# adapter_1x1.net
KiCad netlist of a schematic drawn in EAGLE
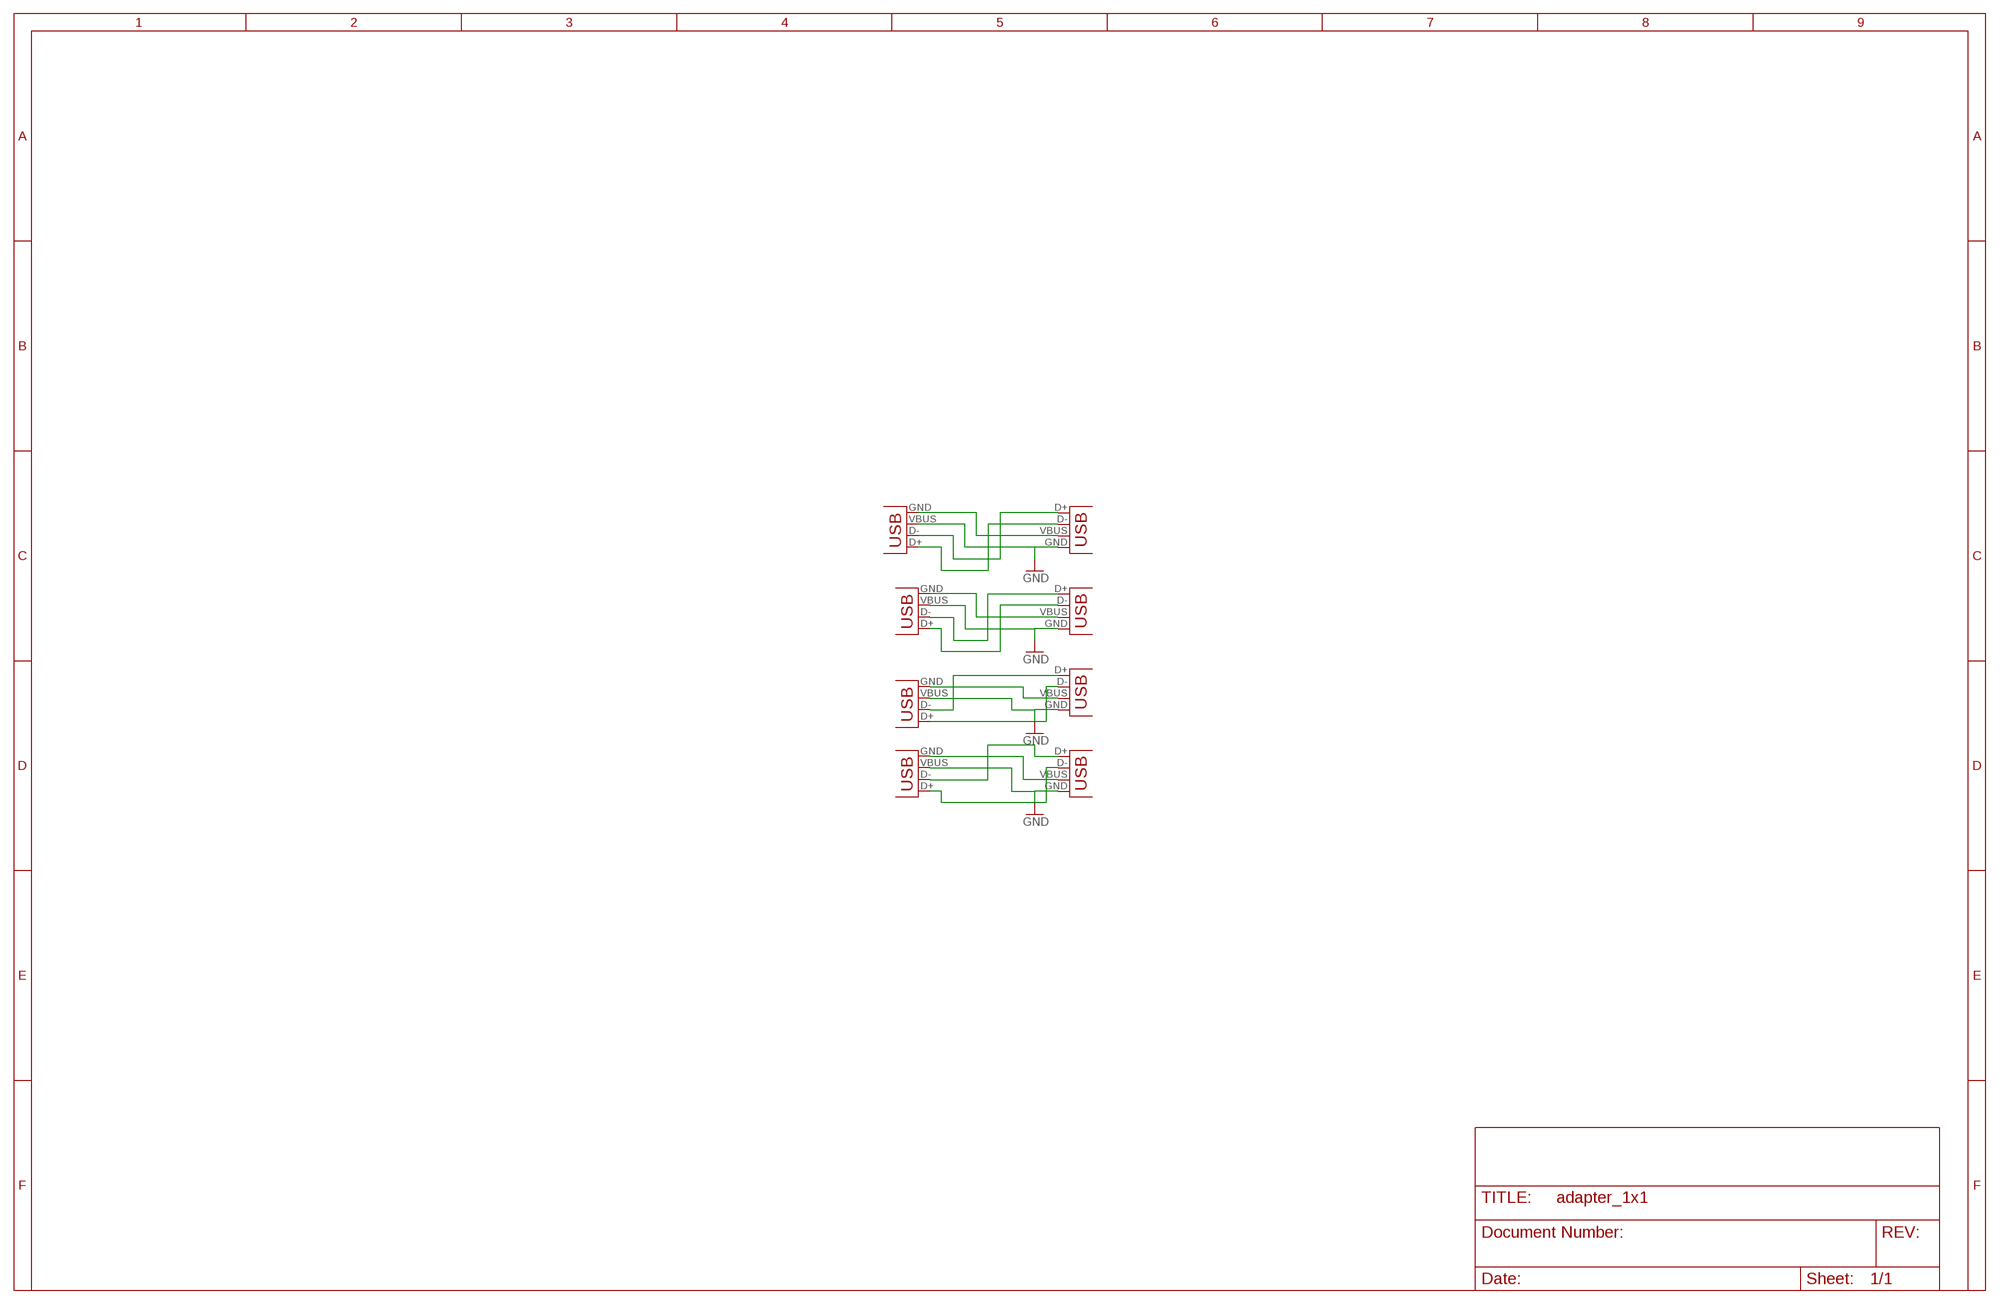
[diagram p0: schematic, sheet 1]

(export (version "E")
  (design (tool "Eeschema 10.0.6"))
  (components
    (comp (ref "X1")
      (value "USB-A-HU")
      (footprint "eagle-import:USB-A-HU")
      (libsource (lib "eagle-import") (part "USB-A-HU"))
    )
    (comp (ref "X2")
      (value "USB-A-HU")
      (footprint "eagle-import:USB-A-HU")
      (libsource (lib "eagle-import") (part "USB-A-HU"))
    )
    (comp (ref "X3")
      (value "USB-A-HU")
      (footprint "eagle-import:USB-A-HU")
      (libsource (lib "eagle-import") (part "USB-A-HU"))
    )
    (comp (ref "X4")
      (value "USB-A-HU")
      (footprint "eagle-import:USB-A-HU")
      (libsource (lib "eagle-import") (part "USB-A-HU"))
    )
    (comp (ref "X5")
      (value "USB-A-HU")
      (footprint "eagle-import:USB-A-HU")
      (libsource (lib "eagle-import") (part "USB-A-HU"))
    )
    (comp (ref "X6")
      (value "USB-A-HU")
      (footprint "eagle-import:USB-A-HU")
      (libsource (lib "eagle-import") (part "USB-A-HU"))
    )
    (comp (ref "X7")
      (value "USB-A-HU")
      (footprint "eagle-import:USB-A-HU")
      (libsource (lib "eagle-import") (part "USB-A-HU"))
    )
    (comp (ref "X8")
      (value "USB-A-HU")
      (footprint "eagle-import:USB-A-HU")
      (libsource (lib "eagle-import") (part "USB-A-HU"))
    )
  )
  (nets
    (net (code "1") (name "GND") (class "Default")
      (node (ref "X1") (pin "GND") (pinfunction "GND_GND") (pintype "bidirectional"))
      (node (ref "X2") (pin "GND") (pinfunction "GND_GND") (pintype "bidirectional"))
      (node (ref "X3") (pin "GND") (pinfunction "GND_GND") (pintype "bidirectional"))
      (node (ref "X4") (pin "GND") (pinfunction "GND_GND") (pintype "bidirectional"))
      (node (ref "X5") (pin "VBUS") (pinfunction "VBUS_VBUS") (pintype "bidirectional"))
      (node (ref "X6") (pin "VBUS") (pinfunction "VBUS_VBUS") (pintype "bidirectional"))
      (node (ref "X7") (pin "VBUS") (pinfunction "VBUS_VBUS") (pintype "bidirectional"))
      (node (ref "X8") (pin "VBUS") (pinfunction "VBUS_VBUS") (pintype "bidirectional"))
    )
    (net (code "2") (name "Net-(X1-PadD+)") (class "Default")
      (node (ref "X1") (pin "D+") (pinfunction "D+_D+") (pintype "bidirectional"))
      (node (ref "X8") (pin "D-") (pinfunction "D-_D-") (pintype "bidirectional"))
    )
    (net (code "3") (name "Net-(X1-PadD-)") (class "Default")
      (node (ref "X1") (pin "D-") (pinfunction "D-_D-") (pintype "bidirectional"))
      (node (ref "X8") (pin "D+") (pinfunction "D+_D+") (pintype "bidirectional"))
    )
    (net (code "4") (name "Net-(X1-PadVBUS)") (class "Default")
      (node (ref "X1") (pin "VBUS") (pinfunction "VBUS_VBUS") (pintype "bidirectional"))
      (node (ref "X8") (pin "GND") (pinfunction "GND_GND") (pintype "bidirectional"))
    )
    (net (code "5") (name "Net-(X2-PadD+)") (class "Default")
      (node (ref "X2") (pin "D+") (pinfunction "D+_D+") (pintype "bidirectional"))
      (node (ref "X7") (pin "D-") (pinfunction "D-_D-") (pintype "bidirectional"))
    )
    (net (code "6") (name "Net-(X2-PadD-)") (class "Default")
      (node (ref "X2") (pin "D-") (pinfunction "D-_D-") (pintype "bidirectional"))
      (node (ref "X7") (pin "D+") (pinfunction "D+_D+") (pintype "bidirectional"))
    )
    (net (code "7") (name "Net-(X2-PadVBUS)") (class "Default")
      (node (ref "X2") (pin "VBUS") (pinfunction "VBUS_VBUS") (pintype "bidirectional"))
      (node (ref "X7") (pin "GND") (pinfunction "GND_GND") (pintype "bidirectional"))
    )
    (net (code "8") (name "Net-(X3-PadD+)") (class "Default")
      (node (ref "X3") (pin "D+") (pinfunction "D+_D+") (pintype "bidirectional"))
      (node (ref "X6") (pin "D-") (pinfunction "D-_D-") (pintype "bidirectional"))
    )
    (net (code "9") (name "Net-(X3-PadD-)") (class "Default")
      (node (ref "X3") (pin "D-") (pinfunction "D-_D-") (pintype "bidirectional"))
      (node (ref "X6") (pin "D+") (pinfunction "D+_D+") (pintype "bidirectional"))
    )
    (net (code "10") (name "Net-(X3-PadVBUS)") (class "Default")
      (node (ref "X3") (pin "VBUS") (pinfunction "VBUS_VBUS") (pintype "bidirectional"))
      (node (ref "X6") (pin "GND") (pinfunction "GND_GND") (pintype "bidirectional"))
    )
    (net (code "11") (name "Net-(X4-PadD+)") (class "Default")
      (node (ref "X4") (pin "D+") (pinfunction "D+_D+") (pintype "bidirectional"))
      (node (ref "X5") (pin "D-") (pinfunction "D-_D-") (pintype "bidirectional"))
    )
    (net (code "12") (name "Net-(X4-PadD-)") (class "Default")
      (node (ref "X4") (pin "D-") (pinfunction "D-_D-") (pintype "bidirectional"))
      (node (ref "X5") (pin "D+") (pinfunction "D+_D+") (pintype "bidirectional"))
    )
    (net (code "13") (name "Net-(X4-PadVBUS)") (class "Default")
      (node (ref "X4") (pin "VBUS") (pinfunction "VBUS_VBUS") (pintype "bidirectional"))
      (node (ref "X5") (pin "GND") (pinfunction "GND_GND") (pintype "bidirectional"))
    )
  )
)
